# Sheet1.net
KiCad netlist of a schematic drawn in Altium Designer
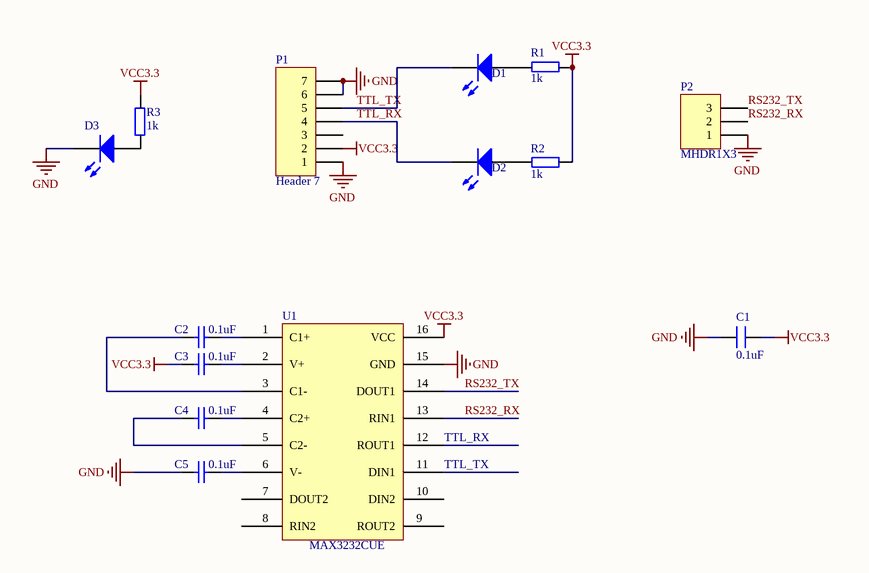
[diagram p0: Sheet1.SchDoc]

(export (version "E")
  (design (tool "Eeschema 10.0.6"))
  (components
    (comp (ref "C1")
      (value "0.1uF")
      (footprint "C0805")
      (libsource (lib "Explorer STM32F407封装库") (part "C_2"))
    )
    (comp (ref "C2")
      (value "0.1uF")
      (footprint "C0805")
      (description "Capacitor")
      (fields (field (name "PUBLISHER") "Altium Limited"))
      (libsource (lib "Miscellaneous Devices") (part "Cap"))
    )
    (comp (ref "C3")
      (value "0.1uF")
      (footprint "C0805")
      (description "Capacitor")
      (fields (field (name "PUBLISHER") "Altium Limited"))
      (libsource (lib "Miscellaneous Devices") (part "Cap"))
    )
    (comp (ref "C4")
      (value "0.1uF")
      (footprint "C0805")
      (description "Capacitor")
      (fields (field (name "PUBLISHER") "Altium Limited"))
      (libsource (lib "Miscellaneous Devices") (part "Cap"))
    )
    (comp (ref "C5")
      (value "0.1uF")
      (footprint "C0805")
      (description "Capacitor")
      (fields (field (name "PUBLISHER") "Altium Limited"))
      (libsource (lib "Miscellaneous Devices") (part "Cap"))
    )
    (comp (ref "D1")
      (value "LED0")
      (footprint "LC-0805_LED_S1")
      (description "Typical INFRARED GaAs LED")
      (fields (field (name "PUBLISHER") "Altium Limited"))
      (libsource (lib "继电器板_1") (part "LED0"))
    )
    (comp (ref "D2")
      (value "LED0")
      (footprint "LC-0805_LED_S1")
      (description "Typical INFRARED GaAs LED")
      (fields (field (name "PUBLISHER") "Altium Limited"))
      (libsource (lib "继电器板_1") (part "LED0"))
    )
    (comp (ref "D3")
      (value "LED0")
      (footprint "LC-0805_LED_S1")
      (description "Typical INFRARED GaAs LED")
      (fields (field (name "PUBLISHER") "Altium Limited"))
      (libsource (lib "继电器板_1") (part "LED0"))
    )
    (comp (ref "P1")
      (value "Header 7")
      (footprint "AS50-T27")
      (description "Header, 7-Pin")
      (fields (field (name "PUBLISHER") "Altium Limited"))
      (libsource (lib "Miscellaneous Connectors") (part "Header 7"))
    )
    (comp (ref "P2")
      (value "MHDR1X3")
      (footprint "DZ-3-3.5")
      (description "Header, 3-Pin")
      (fields (field (name "PUBLISHER") "Altium Limited"))
      (libsource (lib "Miscellaneous Connectors") (part "MHDR1X3"))
    )
    (comp (ref "R1") (value "1k") (footprint "0805") (libsource (lib "Explorer STM32F407封装库") (part "R_2")))
    (comp (ref "R2") (value "1k") (footprint "0805") (libsource (lib "Explorer STM32F407封装库") (part "R_2")))
    (comp (ref "R3") (value "1k") (footprint "0805") (libsource (lib "Explorer STM32F407封装库") (part "R_2")))
    (comp (ref "U1")
      (value "MAX3232CUE")
      (footprint "SO-16")
      (libsource (lib "Smart_board_v1") (part "MAX3232CUE"))
    )
  )
  (nets
    (net (code "1") (name "/RS232_RX") (class "Default")
      (node (ref "P2") (pin "2") (pinfunction "2_2") (pintype "passive"))
      (node (ref "U1") (pin "13") (pinfunction "RIN1_13") (pintype "passive"))
    )
    (net (code "2") (name "/RS232_TX") (class "Default")
      (node (ref "P2") (pin "3") (pinfunction "3_3") (pintype "passive"))
      (node (ref "U1") (pin "14") (pinfunction "DOUT1_14") (pintype "passive"))
    )
    (net (code "3") (name "/TTL_RX") (class "Default")
      (node (ref "D2") (pin "K") (pinfunction "K_K") (pintype "passive"))
      (node (ref "P1") (pin "4") (pinfunction "4_4") (pintype "passive"))
      (node (ref "U1") (pin "12") (pinfunction "ROUT1_12") (pintype "passive"))
    )
    (net (code "4") (name "/TTL_TX") (class "Default")
      (node (ref "D1") (pin "K") (pinfunction "K_K") (pintype "passive"))
      (node (ref "P1") (pin "5") (pinfunction "5_5") (pintype "passive"))
      (node (ref "U1") (pin "11") (pinfunction "DIN1_11") (pintype "passive"))
    )
    (net (code "5") (name "GND") (class "Default")
      (node (ref "C1") (pin "1") (pintype "passive"))
      (node (ref "C5") (pin "2") (pinfunction "2_2") (pintype "passive"))
      (node (ref "D3") (pin "K") (pinfunction "K_K") (pintype "passive"))
      (node (ref "P1") (pin "1") (pinfunction "1_1") (pintype "passive"))
      (node (ref "P1") (pin "6") (pinfunction "6_6") (pintype "passive"))
      (node (ref "P1") (pin "7") (pinfunction "7_7") (pintype "passive"))
      (node (ref "P2") (pin "1") (pinfunction "1_1") (pintype "passive"))
      (node (ref "U1") (pin "15") (pinfunction "GND_15") (pintype "passive"))
    )
    (net (code "6") (name "Net-(D1-PadA)") (class "Default")
      (node (ref "D1") (pin "A") (pinfunction "A_A") (pintype "passive"))
      (node (ref "R1") (pin "2") (pintype "passive"))
    )
    (net (code "7") (name "Net-(D2-PadA)") (class "Default")
      (node (ref "D2") (pin "A") (pinfunction "A_A") (pintype "passive"))
      (node (ref "R2") (pin "1") (pintype "passive"))
    )
    (net (code "8") (name "Net-(D3-PadA)") (class "Default")
      (node (ref "D3") (pin "A") (pinfunction "A_A") (pintype "passive"))
      (node (ref "R3") (pin "2") (pintype "passive"))
    )
    (net (code "9") (name "Net-(U1-C1+)") (class "Default")
      (node (ref "C2") (pin "1") (pinfunction "1_1") (pintype "passive"))
      (node (ref "U1") (pin "1") (pinfunction "C1+_1") (pintype "passive"))
    )
    (net (code "10") (name "Net-(U1-C1-)") (class "Default")
      (node (ref "C2") (pin "2") (pinfunction "2_2") (pintype "passive"))
      (node (ref "U1") (pin "3") (pinfunction "C1-_3") (pintype "passive"))
    )
    (net (code "11") (name "Net-(U1-C2+)") (class "Default")
      (node (ref "C4") (pin "1") (pinfunction "1_1") (pintype "passive"))
      (node (ref "U1") (pin "4") (pinfunction "C2+_4") (pintype "passive"))
    )
    (net (code "12") (name "Net-(U1-C2-)") (class "Default")
      (node (ref "C4") (pin "2") (pinfunction "2_2") (pintype "passive"))
      (node (ref "U1") (pin "5") (pinfunction "C2-_5") (pintype "passive"))
    )
    (net (code "13") (name "Net-(U1-V+)") (class "Default")
      (node (ref "C3") (pin "1") (pinfunction "1_1") (pintype "passive"))
      (node (ref "U1") (pin "2") (pinfunction "V+_2") (pintype "passive"))
    )
    (net (code "14") (name "Net-(U1-V-)") (class "Default")
      (node (ref "C5") (pin "1") (pinfunction "1_1") (pintype "passive"))
      (node (ref "U1") (pin "6") (pinfunction "V-_6") (pintype "passive"))
    )
    (net (code "15") (name "VCC3.3") (class "Default")
      (node (ref "C1") (pin "2") (pintype "passive"))
      (node (ref "C3") (pin "2") (pinfunction "2_2") (pintype "passive"))
      (node (ref "P1") (pin "2") (pinfunction "2_2") (pintype "passive"))
      (node (ref "R1") (pin "1") (pintype "passive"))
      (node (ref "R2") (pin "2") (pintype "passive"))
      (node (ref "R3") (pin "1") (pintype "passive"))
      (node (ref "U1") (pin "16") (pinfunction "VCC_16") (pintype "passive"))
    )
    (net (code "16") (name "unconnected-(P1-Pad3)") (class "Default")
      (node (ref "P1") (pin "3") (pinfunction "3_3") (pintype "passive"))
    )
    (net (code "17") (name "unconnected-(U1-DIN2-Pad10)") (class "Default")
      (node (ref "U1") (pin "10") (pinfunction "DIN2_10") (pintype "passive"))
    )
    (net (code "18") (name "unconnected-(U1-DOUT2-Pad7)") (class "Default")
      (node (ref "U1") (pin "7") (pinfunction "DOUT2_7") (pintype "passive"))
    )
    (net (code "19") (name "unconnected-(U1-RIN2-Pad8)") (class "Default")
      (node (ref "U1") (pin "8") (pinfunction "RIN2_8") (pintype "passive"))
    )
    (net (code "20") (name "unconnected-(U1-ROUT2-Pad9)") (class "Default")
      (node (ref "U1") (pin "9") (pinfunction "ROUT2_9") (pintype "passive"))
    )
  )
)
